# USB-C.net
KiCad netlist of a schematic drawn in Altium Designer
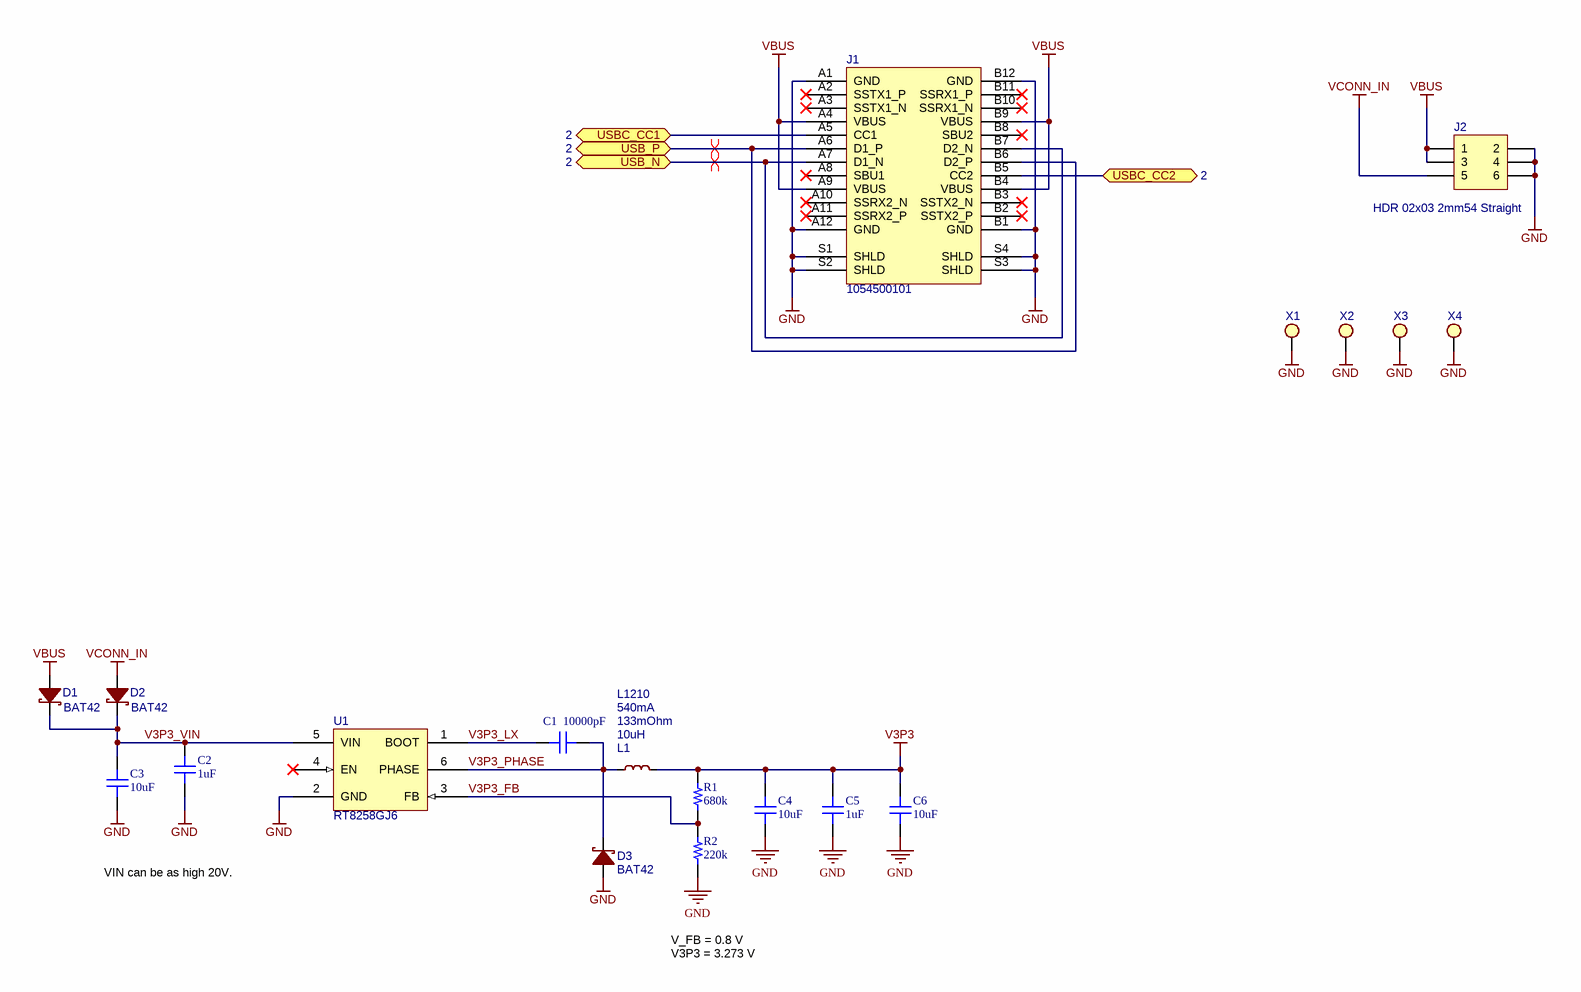
[diagram p0: USB-C.SchDoc]

(export (version "E")
  (design (tool "Eeschema 10.0.6"))
  (components
    (comp (ref "C1")
      (value "10000pF")
      (footprint "CAP 0402/1005")
      (description "CAP CER 10000PF 50V X7R 0402")
      (fields
        (field (name "PART NUMBER") "GCM155R71H103KA55D")
        (field (name "MANUFACTURER") "Murata Electronics North America")
      )
      (libsource (lib "Celestial Library Database") (part "Capacitor"))
    )
    (comp (ref "C2")
      (value "1uF")
      (footprint "CAP 0603/1608")
      (description "CAP CER 1UF 35V X7R 0603")
      (fields
        (field (name "PART NUMBER") "GRM188R7YA105KA12D")
        (field (name "MANUFACTURER") "Murata Electronics North America")
      )
      (libsource (lib "Celestial Library Database") (part "Capacitor"))
    )
    (comp (ref "C3")
      (value "10uF")
      (footprint "CAP 0805/2012")
      (description "CAP CER 10UF 35V X5R 0805")
      (fields
        (field (name "PART NUMBER") "C2012X5R1V106M085AC")
        (field (name "MANUFACTURER") "TDK Corporation")
      )
      (libsource (lib "Celestial Library Database") (part "Capacitor"))
    )
    (comp (ref "C4")
      (value "10uF")
      (footprint "CAP 0805/2012")
      (description "CAP CER 10UF 35V X5R 0805")
      (fields
        (field (name "PART NUMBER") "C2012X5R1V106M085AC")
        (field (name "MANUFACTURER") "TDK Corporation")
      )
      (libsource (lib "Celestial Library Database") (part "Capacitor"))
    )
    (comp (ref "C5")
      (value "1uF")
      (footprint "CAP 0603/1608")
      (description "CAP CER 1UF 35V X7R 0603")
      (fields
        (field (name "PART NUMBER") "GRM188R7YA105KA12D")
        (field (name "MANUFACTURER") "Murata Electronics North America")
      )
      (libsource (lib "Celestial Library Database") (part "Capacitor"))
    )
    (comp (ref "C6")
      (value "10uF")
      (footprint "CAP 0805/2012")
      (description "CAP CER 10UF 35V X5R 0805")
      (fields
        (field (name "PART NUMBER") "C2012X5R1V106M085AC")
        (field (name "MANUFACTURER") "TDK Corporation")
      )
      (libsource (lib "Celestial Library Database") (part "Capacitor"))
    )
    (comp (ref "D1")
      (value "BAT42")
      (footprint "SOD-123")
      (fields (field (name "MANUFACTURER") "MacroFab") (field (name "Comment") "MF-DIO-SOD123-BAT42"))
      (libsource (lib "ReclaimerLabs") (part "DIODE_SCHOTTKY"))
    )
    (comp (ref "D2")
      (value "BAT42")
      (footprint "SOD-123")
      (fields (field (name "MANUFACTURER") "MacroFab") (field (name "Comment") "MF-DIO-SOD123-BAT42"))
      (libsource (lib "ReclaimerLabs") (part "DIODE_SCHOTTKY"))
    )
    (comp (ref "D3")
      (value "BAT42")
      (footprint "SOD-123")
      (fields (field (name "Comment") "MF-DIO-SOD123-BAT42"))
      (libsource (lib "ReclaimerLabs") (part "DIODE_SCHOTTKY"))
    )
    (comp (ref "J1")
      (value "1054500101")
      (footprint "1054500101")
      (fields (field (name "MANUFACTURER") "Molex"))
      (libsource (lib "ReclaimerLabs") (part "USB-C_RECPT"))
    )
    (comp (ref "J2")
      (value "HDR 02x03 2mm54 Straight")
      (footprint "CONN_HEADER_02x03_2mm54_Straight")
      (fields (field (name "Comment") "MF-CON-2.54mm-2x3"))
      (libsource (lib "ReclaimerLabs") (part "CONN_HEADER_02x03_2mm54_Straight"))
    )
    (comp (ref "L1")
      (value "10uH")
      (footprint "L1210")
      (fields
        (field (name "DCR") "133mOhm")
        (field (name "CURRENT") "540mA")
        (field (name "Comment") "MF-IND-1210-10uH")
      )
      (libsource (lib "ReclaimerLabs") (part "INDUCTOR"))
    )
    (comp (ref "R1")
      (value "680k")
      (footprint "RES 0402/1005")
      (description "RES SMD 680K OHM 5% 1/10W 0402")
      (fields
        (field (name "PART NUMBER") "ERJ-2GEJ684X")
        (field (name "MANUFACTURER") "Panasonic Electronic Components")
      )
      (libsource (lib "Celestial Library Database") (part "Resistor"))
    )
    (comp (ref "R2")
      (value "220k")
      (footprint "RES 0402/1005")
      (description "RES SMD 220K OHM 5% 1/10W 0402")
      (fields
        (field (name "PART NUMBER") "ERJ-2GEJ224X")
        (field (name "MANUFACTURER") "Panasonic Electronic Components")
      )
      (libsource (lib "Celestial Library Database") (part "Resistor"))
    )
    (comp (ref "U1")
      (value "RT8258GJ6")
      (footprint "SOT23-6")
      (libsource (lib "ReclaimerLabs") (part "BUCK_RT8258GJ6"))
    )
    (comp (ref "X1") (value "MTHOLE") (libsource (lib "ReclaimerLabs") (part "MTHOLE")))
    (comp (ref "X2") (value "MTHOLE") (libsource (lib "ReclaimerLabs") (part "MTHOLE")))
    (comp (ref "X3") (value "MTHOLE") (libsource (lib "ReclaimerLabs") (part "MTHOLE")))
    (comp (ref "X4") (value "MTHOLE") (libsource (lib "ReclaimerLabs") (part "MTHOLE")))
  )
  (nets
    (net (code "1") (name "/USBC_CC1") (class "Default")
      (node (ref "J1") (pin "A5") (pinfunction "CC1_A5") (pintype "passive"))
    )
    (net (code "2") (name "/USBC_CC2") (class "Default")
      (node (ref "J1") (pin "B5") (pinfunction "CC2_B5") (pintype "passive"))
    )
    (net (code "3") (name "/USB_N") (class "Default")
      (node (ref "J1") (pin "A7") (pinfunction "D1_N_A7") (pintype "passive"))
      (node (ref "J1") (pin "B7") (pinfunction "D2_N_B7") (pintype "passive"))
    )
    (net (code "4") (name "/USB_P") (class "Default")
      (node (ref "J1") (pin "A6") (pinfunction "D1_P_A6") (pintype "passive"))
      (node (ref "J1") (pin "B6") (pinfunction "D2_P_B6") (pintype "passive"))
    )
    (net (code "5") (name "/V3P3_FB") (class "Default")
      (node (ref "R1") (pin "1") (pinfunction "1_1") (pintype "passive"))
      (node (ref "R2") (pin "2") (pinfunction "2_2") (pintype "passive"))
      (node (ref "U1") (pin "3") (pinfunction "FB_3") (pintype "input"))
    )
    (net (code "6") (name "/V3P3_LX") (class "Default")
      (node (ref "C1") (pin "1") (pinfunction "1_1") (pintype "passive"))
      (node (ref "U1") (pin "1") (pinfunction "BOOT_1") (pintype "power_in"))
    )
    (net (code "7") (name "/V3P3_PHASE") (class "Default")
      (node (ref "C1") (pin "2") (pinfunction "2_2") (pintype "passive"))
      (node (ref "D3") (pin "1") (pinfunction "C1_1") (pintype "passive"))
      (node (ref "L1") (pin "1") (pinfunction "R1_1") (pintype "passive"))
      (node (ref "U1") (pin "6") (pinfunction "PHASE_6") (pintype "power_in"))
    )
    (net (code "8") (name "/V3P3_VIN") (class "Default")
      (node (ref "C2") (pin "1") (pinfunction "1_1") (pintype "passive"))
      (node (ref "C3") (pin "2") (pinfunction "2_2") (pintype "passive"))
      (node (ref "D1") (pin "1") (pinfunction "C1_1") (pintype "passive"))
      (node (ref "D2") (pin "1") (pinfunction "C1_1") (pintype "passive"))
      (node (ref "U1") (pin "5") (pinfunction "VIN_5") (pintype "power_in"))
    )
    (net (code "9") (name "GND") (class "Default")
      (node (ref "C2") (pin "2") (pinfunction "2_2") (pintype "passive"))
      (node (ref "C3") (pin "1") (pinfunction "1_1") (pintype "passive"))
      (node (ref "C4") (pin "1") (pinfunction "1_1") (pintype "passive"))
      (node (ref "C5") (pin "2") (pinfunction "2_2") (pintype "passive"))
      (node (ref "C6") (pin "1") (pinfunction "1_1") (pintype "passive"))
      (node (ref "D3") (pin "2") (pinfunction "C2_2") (pintype "passive"))
      (node (ref "J1") (pin "A1") (pinfunction "GND_A1") (pintype "passive"))
      (node (ref "J1") (pin "A12") (pinfunction "GND_A12") (pintype "passive"))
      (node (ref "J1") (pin "B1") (pinfunction "GND_B1") (pintype "passive"))
      (node (ref "J1") (pin "B12") (pinfunction "GND_B12") (pintype "passive"))
      (node (ref "J1") (pin "S1") (pinfunction "SHLD_S1") (pintype "passive"))
      (node (ref "J1") (pin "S2") (pinfunction "SHLD_S2") (pintype "passive"))
      (node (ref "J1") (pin "S3") (pinfunction "SHLD_S3") (pintype "passive"))
      (node (ref "J1") (pin "S4") (pinfunction "SHLD_S4") (pintype "passive"))
      (node (ref "J2") (pin "2") (pinfunction "2_2") (pintype "power_in"))
      (node (ref "J2") (pin "4") (pinfunction "4_4") (pintype "power_in"))
      (node (ref "J2") (pin "6") (pinfunction "6_6") (pintype "power_in"))
      (node (ref "R2") (pin "1") (pinfunction "1_1") (pintype "passive"))
      (node (ref "U1") (pin "2") (pinfunction "GND_2") (pintype "passive"))
      (node (ref "X1") (pin "1") (pinfunction "1_1") (pintype "passive"))
      (node (ref "X2") (pin "1") (pinfunction "1_1") (pintype "passive"))
      (node (ref "X3") (pin "1") (pinfunction "1_1") (pintype "passive"))
      (node (ref "X4") (pin "1") (pinfunction "1_1") (pintype "passive"))
    )
    (net (code "10") (name "V3P3") (class "Default")
      (node (ref "C4") (pin "2") (pinfunction "2_2") (pintype "passive"))
      (node (ref "C5") (pin "1") (pinfunction "1_1") (pintype "passive"))
      (node (ref "C6") (pin "2") (pinfunction "2_2") (pintype "passive"))
      (node (ref "L1") (pin "2") (pinfunction "R2_2") (pintype "passive"))
      (node (ref "R1") (pin "2") (pinfunction "2_2") (pintype "passive"))
    )
    (net (code "11") (name "VBUS") (class "Default")
      (node (ref "D1") (pin "2") (pinfunction "C2_2") (pintype "passive"))
      (node (ref "J1") (pin "A4") (pinfunction "VBUS_A4") (pintype "passive"))
      (node (ref "J1") (pin "A9") (pinfunction "VBUS_A9") (pintype "passive"))
      (node (ref "J1") (pin "B4") (pinfunction "VBUS_B4") (pintype "passive"))
      (node (ref "J1") (pin "B9") (pinfunction "VBUS_B9") (pintype "passive"))
      (node (ref "J2") (pin "1") (pinfunction "1_1") (pintype "power_in"))
      (node (ref "J2") (pin "3") (pinfunction "3_3") (pintype "power_in"))
    )
    (net (code "12") (name "VCONN_IN") (class "Default")
      (node (ref "D2") (pin "2") (pinfunction "C2_2") (pintype "passive"))
      (node (ref "J2") (pin "5") (pinfunction "5_5") (pintype "power_in"))
    )
    (net (code "13") (name "unconnected-(J1-SBU1-PadA8)") (class "Default")
      (node (ref "J1") (pin "A8") (pinfunction "SBU1_A8") (pintype "passive+no_connect"))
    )
    (net (code "14") (name "unconnected-(J1-SBU2-PadB8)") (class "Default")
      (node (ref "J1") (pin "B8") (pinfunction "SBU2_B8") (pintype "passive+no_connect"))
    )
    (net (code "15") (name "unconnected-(J1-SSRX1_N-PadB10)") (class "Default")
      (node (ref "J1") (pin "B10") (pinfunction "SSRX1_N_B10") (pintype "passive+no_connect"))
    )
    (net (code "16") (name "unconnected-(J1-SSRX1_P-PadB11)") (class "Default")
      (node (ref "J1") (pin "B11") (pinfunction "SSRX1_P_B11") (pintype "passive+no_connect"))
    )
    (net (code "17") (name "unconnected-(J1-SSRX2_N-PadA10)") (class "Default")
      (node (ref "J1") (pin "A10") (pinfunction "SSRX2_N_A10") (pintype "passive+no_connect"))
    )
    (net (code "18") (name "unconnected-(J1-SSRX2_P-PadA11)") (class "Default")
      (node (ref "J1") (pin "A11") (pinfunction "SSRX2_P_A11") (pintype "passive+no_connect"))
    )
    (net (code "19") (name "unconnected-(J1-SSTX1_N-PadA3)") (class "Default")
      (node (ref "J1") (pin "A3") (pinfunction "SSTX1_N_A3") (pintype "passive+no_connect"))
    )
    (net (code "20") (name "unconnected-(J1-SSTX1_P-PadA2)") (class "Default")
      (node (ref "J1") (pin "A2") (pinfunction "SSTX1_P_A2") (pintype "passive+no_connect"))
    )
    (net (code "21") (name "unconnected-(J1-SSTX2_N-PadB3)") (class "Default")
      (node (ref "J1") (pin "B3") (pinfunction "SSTX2_N_B3") (pintype "passive+no_connect"))
    )
    (net (code "22") (name "unconnected-(J1-SSTX2_P-PadB2)") (class "Default")
      (node (ref "J1") (pin "B2") (pinfunction "SSTX2_P_B2") (pintype "passive+no_connect"))
    )
    (net (code "23") (name "unconnected-(U1-EN-Pad4)") (class "Default")
      (node (ref "U1") (pin "4") (pinfunction "EN_4") (pintype "input+no_connect"))
    )
  )
)
